# Connecteurs.net
KiCad netlist of a schematic drawn in Altium Designer
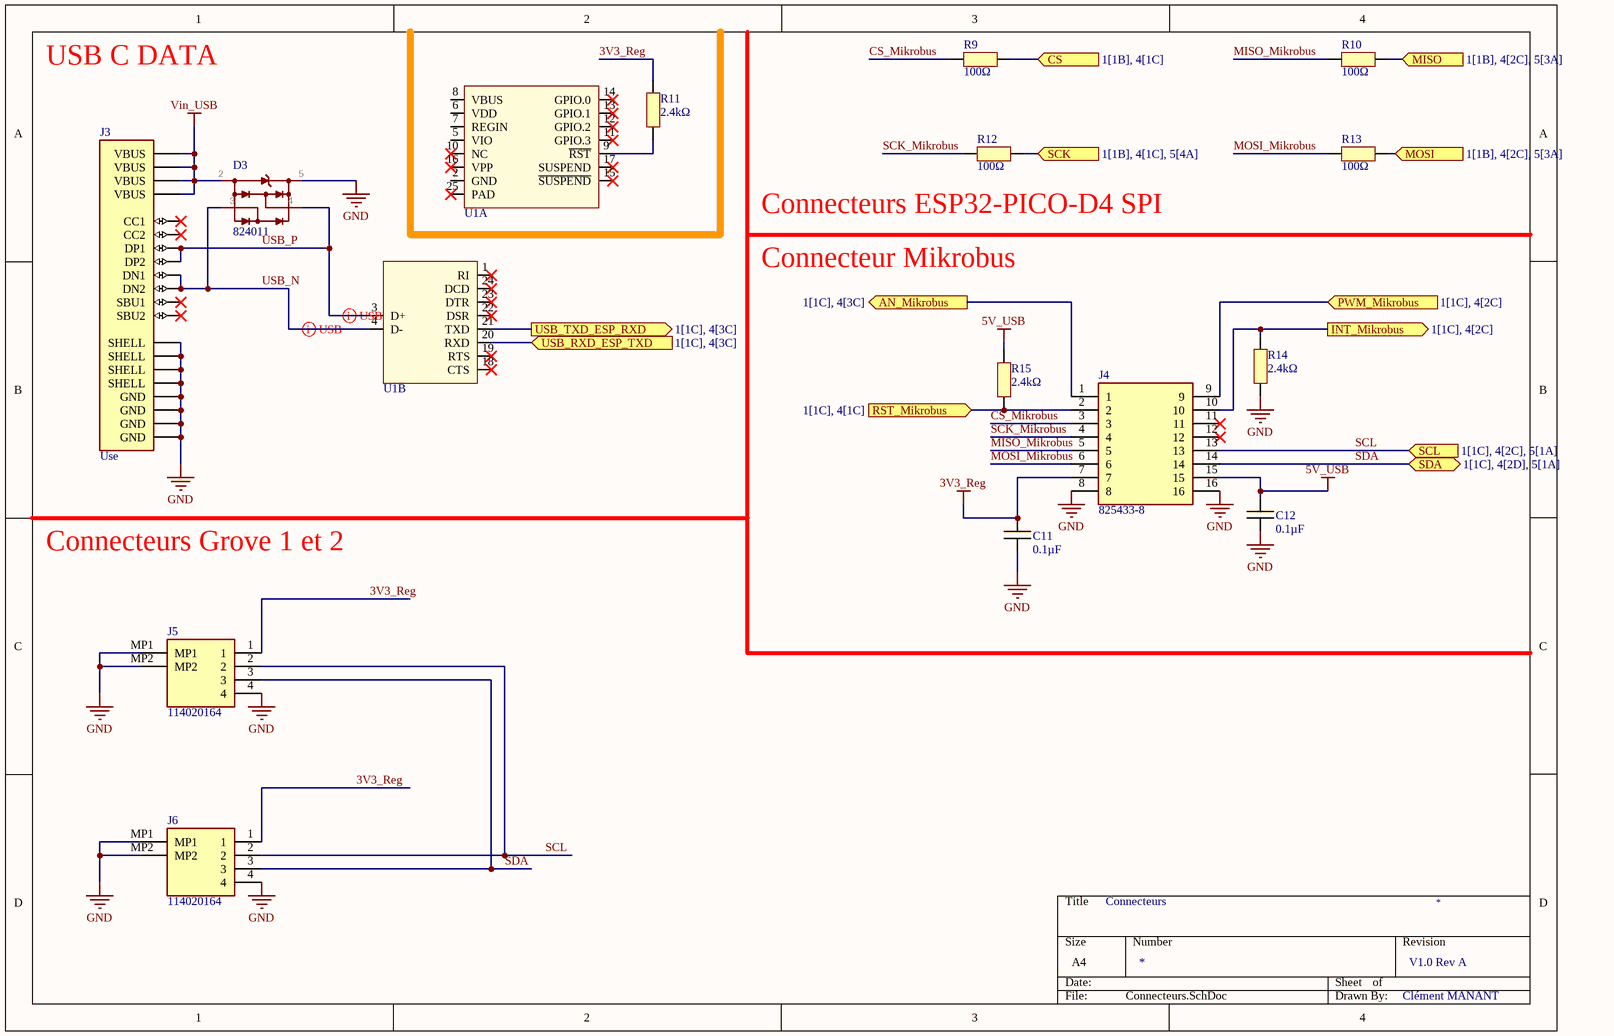
[diagram p0: Connecteurs.SchDoc]

(export (version "E")
  (design (tool "Eeschema 10.0.6"))
  (components
    (comp (ref "C11")
      (value "0.1µF")
      (footprint "CAPC1005X06N")
      (libsource (lib "SCHLibrary") (part "Capacitor"))
    )
    (comp (ref "C12")
      (value "0.1µF")
      (footprint "CAPC1005X06N")
      (libsource (lib "SCHLibrary") (part "Capacitor"))
    )
    (comp (ref "D3") (value "824011") (footprint "824011") (libsource (lib "SCHLibrary") (part "824011")))
    (comp (ref "J3")
      (value "Use")
      (footprint "USB4085-GF-A")
      (description "Connecteurs USB USB Type C, 2.0, Rec, TH , G/F, RA , Top Mnt, T & R")
      (libsource (lib "SCHLibrary") (part "USB4085-GF-A"))
    )
    (comp (ref "J4")
      (value "825433-8")
      (footprint "Connect-Mikronus")
      (description "Headers & Wire Housings 8P double for connection mikrobus")
      (fields (field (name "MOUSER PART NUMBER") "571-825433-8"))
      (libsource (lib "SCHLibrary") (part "Connect-Mikrobus"))
    )
    (comp (ref "J5")
      (value "114020164")
      (footprint "114020164")
      (description "Seeed Studio Accessories Grove Female Header - SMD-4P-2.0mm-90D-20Pcs")
      (fields (field (name "MOUSER PART NUMBER") "713-114020164"))
      (libsource (lib "SCHLibrary") (part "114020164"))
    )
    (comp (ref "J6")
      (value "114020164")
      (footprint "114020164")
      (description "Seeed Studio Accessories Grove Female Header - SMD-4P-2.0mm-90D-20Pcs")
      (fields (field (name "MOUSER PART NUMBER") "713-114020164"))
      (libsource (lib "SCHLibrary") (part "114020164"))
    )
    (comp (ref "R9")
      (value "100Ω")
      (footprint "RESC1005X06N")
      (libsource (lib "SCHLibrary") (part "Resistor"))
    )
    (comp (ref "R10")
      (value "100Ω")
      (footprint "RESC1005X06N")
      (libsource (lib "SCHLibrary") (part "Resistor"))
    )
    (comp (ref "R11") (value "2.4kΩ") (footprint "RESC1005X06N") (libsource (lib "") (part "Resistor_1")))
    (comp (ref "R12")
      (value "100Ω")
      (footprint "RESC1005X06N")
      (libsource (lib "SCHLibrary") (part "Resistor"))
    )
    (comp (ref "R13")
      (value "100Ω")
      (footprint "RESC1005X06N")
      (libsource (lib "SCHLibrary") (part "Resistor"))
    )
    (comp (ref "R14") (value "2.4kΩ") (footprint "RESC1005X06N") (libsource (lib "") (part "Resistor_1")))
    (comp (ref "R15") (value "2.4kΩ") (footprint "RESC1005X06N") (libsource (lib "") (part "Resistor_1")))
    (comp (ref "U1")
      (value "CP2104-F03-GM")
      (footprint "PQFN50P400X400X80_HS-25N")
      (description "USB Bridge, USB to UART USB 2.0 UART Interface 24-QFN (4x4)")
      (libsource (lib "SCHLibrary") (part "USBBridge"))
    )
  )
  (nets
    (net (code "1") (name "/AN_Mikrobus") (class "Default")
      (node (ref "J4") (pin "1") (pinfunction "1_1") (pintype "passive"))
    )
    (net (code "2") (name "/CS") (class "Default")
      (node (ref "R9") (pin "2") (pinfunction "2_2") (pintype "passive"))
    )
    (net (code "3") (name "/CS_Mikrobus") (class "Default")
      (node (ref "J4") (pin "3") (pinfunction "3_3") (pintype "passive"))
      (node (ref "R9") (pin "1") (pinfunction "1_1") (pintype "passive"))
    )
    (net (code "4") (name "/INT_Mikrobus") (class "Default")
      (node (ref "J4") (pin "10") (pinfunction "10_10") (pintype "passive"))
      (node (ref "R14") (pin "2") (pinfunction "2_2") (pintype "passive"))
    )
    (net (code "5") (name "/MISO") (class "Default")
      (node (ref "R10") (pin "2") (pinfunction "2_2") (pintype "passive"))
    )
    (net (code "6") (name "/MISO_Mikrobus") (class "Default")
      (node (ref "J4") (pin "5") (pinfunction "5_5") (pintype "passive"))
      (node (ref "R10") (pin "1") (pinfunction "1_1") (pintype "passive"))
    )
    (net (code "7") (name "/MOSI") (class "Default")
      (node (ref "R13") (pin "2") (pinfunction "2_2") (pintype "passive"))
    )
    (net (code "8") (name "/MOSI_Mikrobus") (class "Default")
      (node (ref "J4") (pin "6") (pinfunction "6_6") (pintype "passive"))
      (node (ref "R13") (pin "1") (pinfunction "1_1") (pintype "passive"))
    )
    (net (code "9") (name "/PWM_Mikrobus") (class "Default")
      (node (ref "J4") (pin "9") (pinfunction "9_9") (pintype "passive"))
    )
    (net (code "10") (name "/RST_Mikrobus") (class "Default")
      (node (ref "J4") (pin "2") (pinfunction "2_2") (pintype "passive"))
      (node (ref "R15") (pin "1") (pinfunction "1_1") (pintype "passive"))
    )
    (net (code "11") (name "/SCK") (class "Default")
      (node (ref "R12") (pin "2") (pinfunction "2_2") (pintype "passive"))
    )
    (net (code "12") (name "/SCK_Mikrobus") (class "Default")
      (node (ref "J4") (pin "4") (pinfunction "4_4") (pintype "passive"))
      (node (ref "R12") (pin "1") (pinfunction "1_1") (pintype "passive"))
    )
    (net (code "13") (name "/SCL") (class "Default")
      (node (ref "J4") (pin "13") (pinfunction "13_13") (pintype "passive"))
      (node (ref "J5") (pin "2") (pinfunction "2_2") (pintype "passive"))
      (node (ref "J6") (pin "2") (pinfunction "2_2") (pintype "passive"))
    )
    (net (code "14") (name "/SDA") (class "Default")
      (node (ref "J4") (pin "14") (pinfunction "14_14") (pintype "passive"))
      (node (ref "J5") (pin "3") (pinfunction "3_3") (pintype "passive"))
      (node (ref "J6") (pin "3") (pinfunction "3_3") (pintype "passive"))
    )
    (net (code "15") (name "/USB_N") (class "Default")
      (node (ref "D3") (pin "3") (pinfunction "1_3") (pintype "passive"))
      (node (ref "J3") (pin "A7") (pinfunction "DN1_A7") (pintype "bidirectional"))
      (node (ref "J3") (pin "B7") (pinfunction "DN2_B7") (pintype "bidirectional"))
      (node (ref "U1") (pin "4") (pinfunction "D-_4") (pintype "passive"))
    )
    (net (code "16") (name "/USB_P") (class "Default")
      (node (ref "D3") (pin "4") (pinfunction "2_4") (pintype "passive"))
      (node (ref "J3") (pin "A6") (pinfunction "DP1_A6") (pintype "bidirectional"))
      (node (ref "J3") (pin "B6") (pinfunction "DP2_B6") (pintype "bidirectional"))
      (node (ref "U1") (pin "3") (pinfunction "D+_3") (pintype "passive"))
    )
    (net (code "17") (name "/USB_RXD_ESP_TXD") (class "Default")
      (node (ref "U1") (pin "20") (pinfunction "RXD_20") (pintype "passive"))
    )
    (net (code "18") (name "/USB_TXD_ESP_RXD") (class "Default")
      (node (ref "U1") (pin "21") (pinfunction "TXD_21") (pintype "passive"))
    )
    (net (code "19") (name "3V3_Reg") (class "Default")
      (node (ref "C11") (pin "1") (pinfunction "1_1") (pintype "passive"))
      (node (ref "J4") (pin "7") (pinfunction "7_7") (pintype "passive"))
      (node (ref "J5") (pin "1") (pinfunction "1_1") (pintype "passive"))
      (node (ref "J6") (pin "1") (pinfunction "1_1") (pintype "passive"))
      (node (ref "R11") (pin "2") (pinfunction "2_2") (pintype "passive"))
    )
    (net (code "20") (name "5V_USB") (class "Default")
      (node (ref "C12") (pin "1") (pinfunction "1_1") (pintype "passive"))
      (node (ref "J4") (pin "15") (pinfunction "15_15") (pintype "passive"))
      (node (ref "R15") (pin "2") (pinfunction "2_2") (pintype "passive"))
    )
    (net (code "21") (name "GND") (class "Default")
      (node (ref "C11") (pin "2") (pinfunction "2_2") (pintype "passive"))
      (node (ref "C12") (pin "2") (pinfunction "2_2") (pintype "passive"))
      (node (ref "D3") (pin "5") (pinfunction "VDD_5") (pintype "power_in"))
      (node (ref "J3") (pin "A1") (pinfunction "GND_A1") (pintype "power_in"))
      (node (ref "J3") (pin "A12") (pinfunction "GND_A12") (pintype "power_in"))
      (node (ref "J3") (pin "B1") (pinfunction "GND_B1") (pintype "power_in"))
      (node (ref "J3") (pin "B12") (pinfunction "GND_B12") (pintype "power_in"))
      (node (ref "J3") (pin "S1") (pinfunction "SHELL_S1") (pintype "passive"))
      (node (ref "J3") (pin "S2") (pinfunction "SHELL_S2") (pintype "passive"))
      (node (ref "J3") (pin "S3") (pinfunction "SHELL_S3") (pintype "passive"))
      (node (ref "J3") (pin "S4") (pinfunction "SHELL_S4") (pintype "passive"))
      (node (ref "J4") (pin "16") (pinfunction "16_16") (pintype "passive"))
      (node (ref "J4") (pin "8") (pinfunction "8_8") (pintype "passive"))
      (node (ref "J5") (pin "4") (pinfunction "4_4") (pintype "passive"))
      (node (ref "J5") (pin "MP1") (pinfunction "MP1_MP1") (pintype "passive"))
      (node (ref "J5") (pin "MP2") (pinfunction "MP2_MP2") (pintype "passive"))
      (node (ref "J6") (pin "4") (pinfunction "4_4") (pintype "passive"))
      (node (ref "J6") (pin "MP1") (pinfunction "MP1_MP1") (pintype "passive"))
      (node (ref "J6") (pin "MP2") (pinfunction "MP2_MP2") (pintype "passive"))
      (node (ref "R14") (pin "1") (pinfunction "1_1") (pintype "passive"))
    )
    (net (code "22") (name "Net-(U1A-~{RST})") (class "Default")
      (node (ref "R11") (pin "1") (pinfunction "1_1") (pintype "passive"))
      (node (ref "U1") (pin "9") (pinfunction "~{RST}_9") (pintype "passive"))
    )
    (net (code "23") (name "Vin_USB") (class "Default")
      (node (ref "D3") (pin "2") (pinfunction "GND_2") (pintype "power_in"))
      (node (ref "J3") (pin "A4") (pinfunction "VBUS_A4") (pintype "power_in"))
      (node (ref "J3") (pin "A9") (pinfunction "VBUS_A9") (pintype "power_in"))
      (node (ref "J3") (pin "B4") (pinfunction "VBUS_B4") (pintype "power_in"))
      (node (ref "J3") (pin "B9") (pinfunction "VBUS_B9") (pintype "power_in"))
    )
    (net (code "24") (name "unconnected-(J3-CC1-PadA5)") (class "Default")
      (node (ref "J3") (pin "A5") (pinfunction "CC1_A5") (pintype "bidirectional+no_connect"))
    )
    (net (code "25") (name "unconnected-(J3-CC2-PadB5)") (class "Default")
      (node (ref "J3") (pin "B5") (pinfunction "CC2_B5") (pintype "bidirectional+no_connect"))
    )
    (net (code "26") (name "unconnected-(J3-SBU1-PadA8)") (class "Default")
      (node (ref "J3") (pin "A8") (pinfunction "SBU1_A8") (pintype "bidirectional+no_connect"))
    )
    (net (code "27") (name "unconnected-(J3-SBU2-PadB8)") (class "Default")
      (node (ref "J3") (pin "B8") (pinfunction "SBU2_B8") (pintype "bidirectional+no_connect"))
    )
    (net (code "28") (name "unconnected-(J4-Pad11)") (class "Default")
      (node (ref "J4") (pin "11") (pinfunction "11_11") (pintype "passive+no_connect"))
    )
    (net (code "29") (name "unconnected-(J4-Pad12)") (class "Default")
      (node (ref "J4") (pin "12") (pinfunction "12_12") (pintype "passive+no_connect"))
    )
    (net (code "30") (name "unconnected-(U1A-GND-Pad2)") (class "Default")
      (node (ref "U1") (pin "2") (pinfunction "GND_2") (pintype "passive"))
    )
    (net (code "31") (name "unconnected-(U1A-GPIO.0-Pad14)") (class "Default")
      (node (ref "U1") (pin "14") (pinfunction "GPIO.0_14") (pintype "passive+no_connect"))
    )
    (net (code "32") (name "unconnected-(U1A-GPIO.1-Pad13)") (class "Default")
      (node (ref "U1") (pin "13") (pinfunction "GPIO.1_13") (pintype "passive+no_connect"))
    )
    (net (code "33") (name "unconnected-(U1A-GPIO.2-Pad12)") (class "Default")
      (node (ref "U1") (pin "12") (pinfunction "GPIO.2_12") (pintype "passive+no_connect"))
    )
    (net (code "34") (name "unconnected-(U1A-GPIO.3-Pad11)") (class "Default")
      (node (ref "U1") (pin "11") (pinfunction "GPIO.3_11") (pintype "passive+no_connect"))
    )
    (net (code "35") (name "unconnected-(U1A-NC-Pad10)") (class "Default")
      (node (ref "U1") (pin "10") (pinfunction "NC_10") (pintype "passive+no_connect"))
    )
    (net (code "36") (name "unconnected-(U1A-PAD-Pad25)") (class "Default")
      (node (ref "U1") (pin "25") (pinfunction "PAD_25") (pintype "passive+no_connect"))
    )
    (net (code "37") (name "unconnected-(U1A-REGIN-Pad7)") (class "Default")
      (node (ref "U1") (pin "7") (pinfunction "REGIN_7") (pintype "passive"))
    )
    (net (code "38") (name "unconnected-(U1A-SUSPEND-Pad17)") (class "Default")
      (node (ref "U1") (pin "17") (pinfunction "SUSPEND_17") (pintype "passive+no_connect"))
    )
    (net (code "39") (name "unconnected-(U1A-VBUS-Pad8)") (class "Default")
      (node (ref "U1") (pin "8") (pinfunction "VBUS_8") (pintype "passive"))
    )
    (net (code "40") (name "unconnected-(U1A-VDD-Pad6)") (class "Default")
      (node (ref "U1") (pin "6") (pinfunction "VDD_6") (pintype "passive"))
    )
    (net (code "41") (name "unconnected-(U1A-VIO-Pad5)") (class "Default")
      (node (ref "U1") (pin "5") (pinfunction "VIO_5") (pintype "passive"))
    )
    (net (code "42") (name "unconnected-(U1A-VPP-Pad16)") (class "Default")
      (node (ref "U1") (pin "16") (pinfunction "VPP_16") (pintype "passive+no_connect"))
    )
    (net (code "43") (name "unconnected-(U1A-~{SUSPEND}-Pad15)") (class "Default")
      (node (ref "U1") (pin "15") (pinfunction "~{SUSPEND}_15") (pintype "passive+no_connect"))
    )
    (net (code "44") (name "unconnected-(U1B-CTS-Pad18)") (class "Default")
      (node (ref "U1") (pin "18") (pinfunction "CTS_18") (pintype "passive+no_connect"))
    )
    (net (code "45") (name "unconnected-(U1B-DCD-Pad24)") (class "Default")
      (node (ref "U1") (pin "24") (pinfunction "DCD_24") (pintype "passive+no_connect"))
    )
    (net (code "46") (name "unconnected-(U1B-DSR-Pad22)") (class "Default")
      (node (ref "U1") (pin "22") (pinfunction "DSR_22") (pintype "passive+no_connect"))
    )
    (net (code "47") (name "unconnected-(U1B-DTR-Pad23)") (class "Default")
      (node (ref "U1") (pin "23") (pinfunction "DTR_23") (pintype "passive+no_connect"))
    )
    (net (code "48") (name "unconnected-(U1B-RI-Pad1)") (class "Default")
      (node (ref "U1") (pin "1") (pinfunction "RI_1") (pintype "passive+no_connect"))
    )
    (net (code "49") (name "unconnected-(U1B-RTS-Pad19)") (class "Default")
      (node (ref "U1") (pin "19") (pinfunction "RTS_19") (pintype "passive+no_connect"))
    )
  )
)
